# step.net
KiCad netlist of a schematic drawn in EAGLE
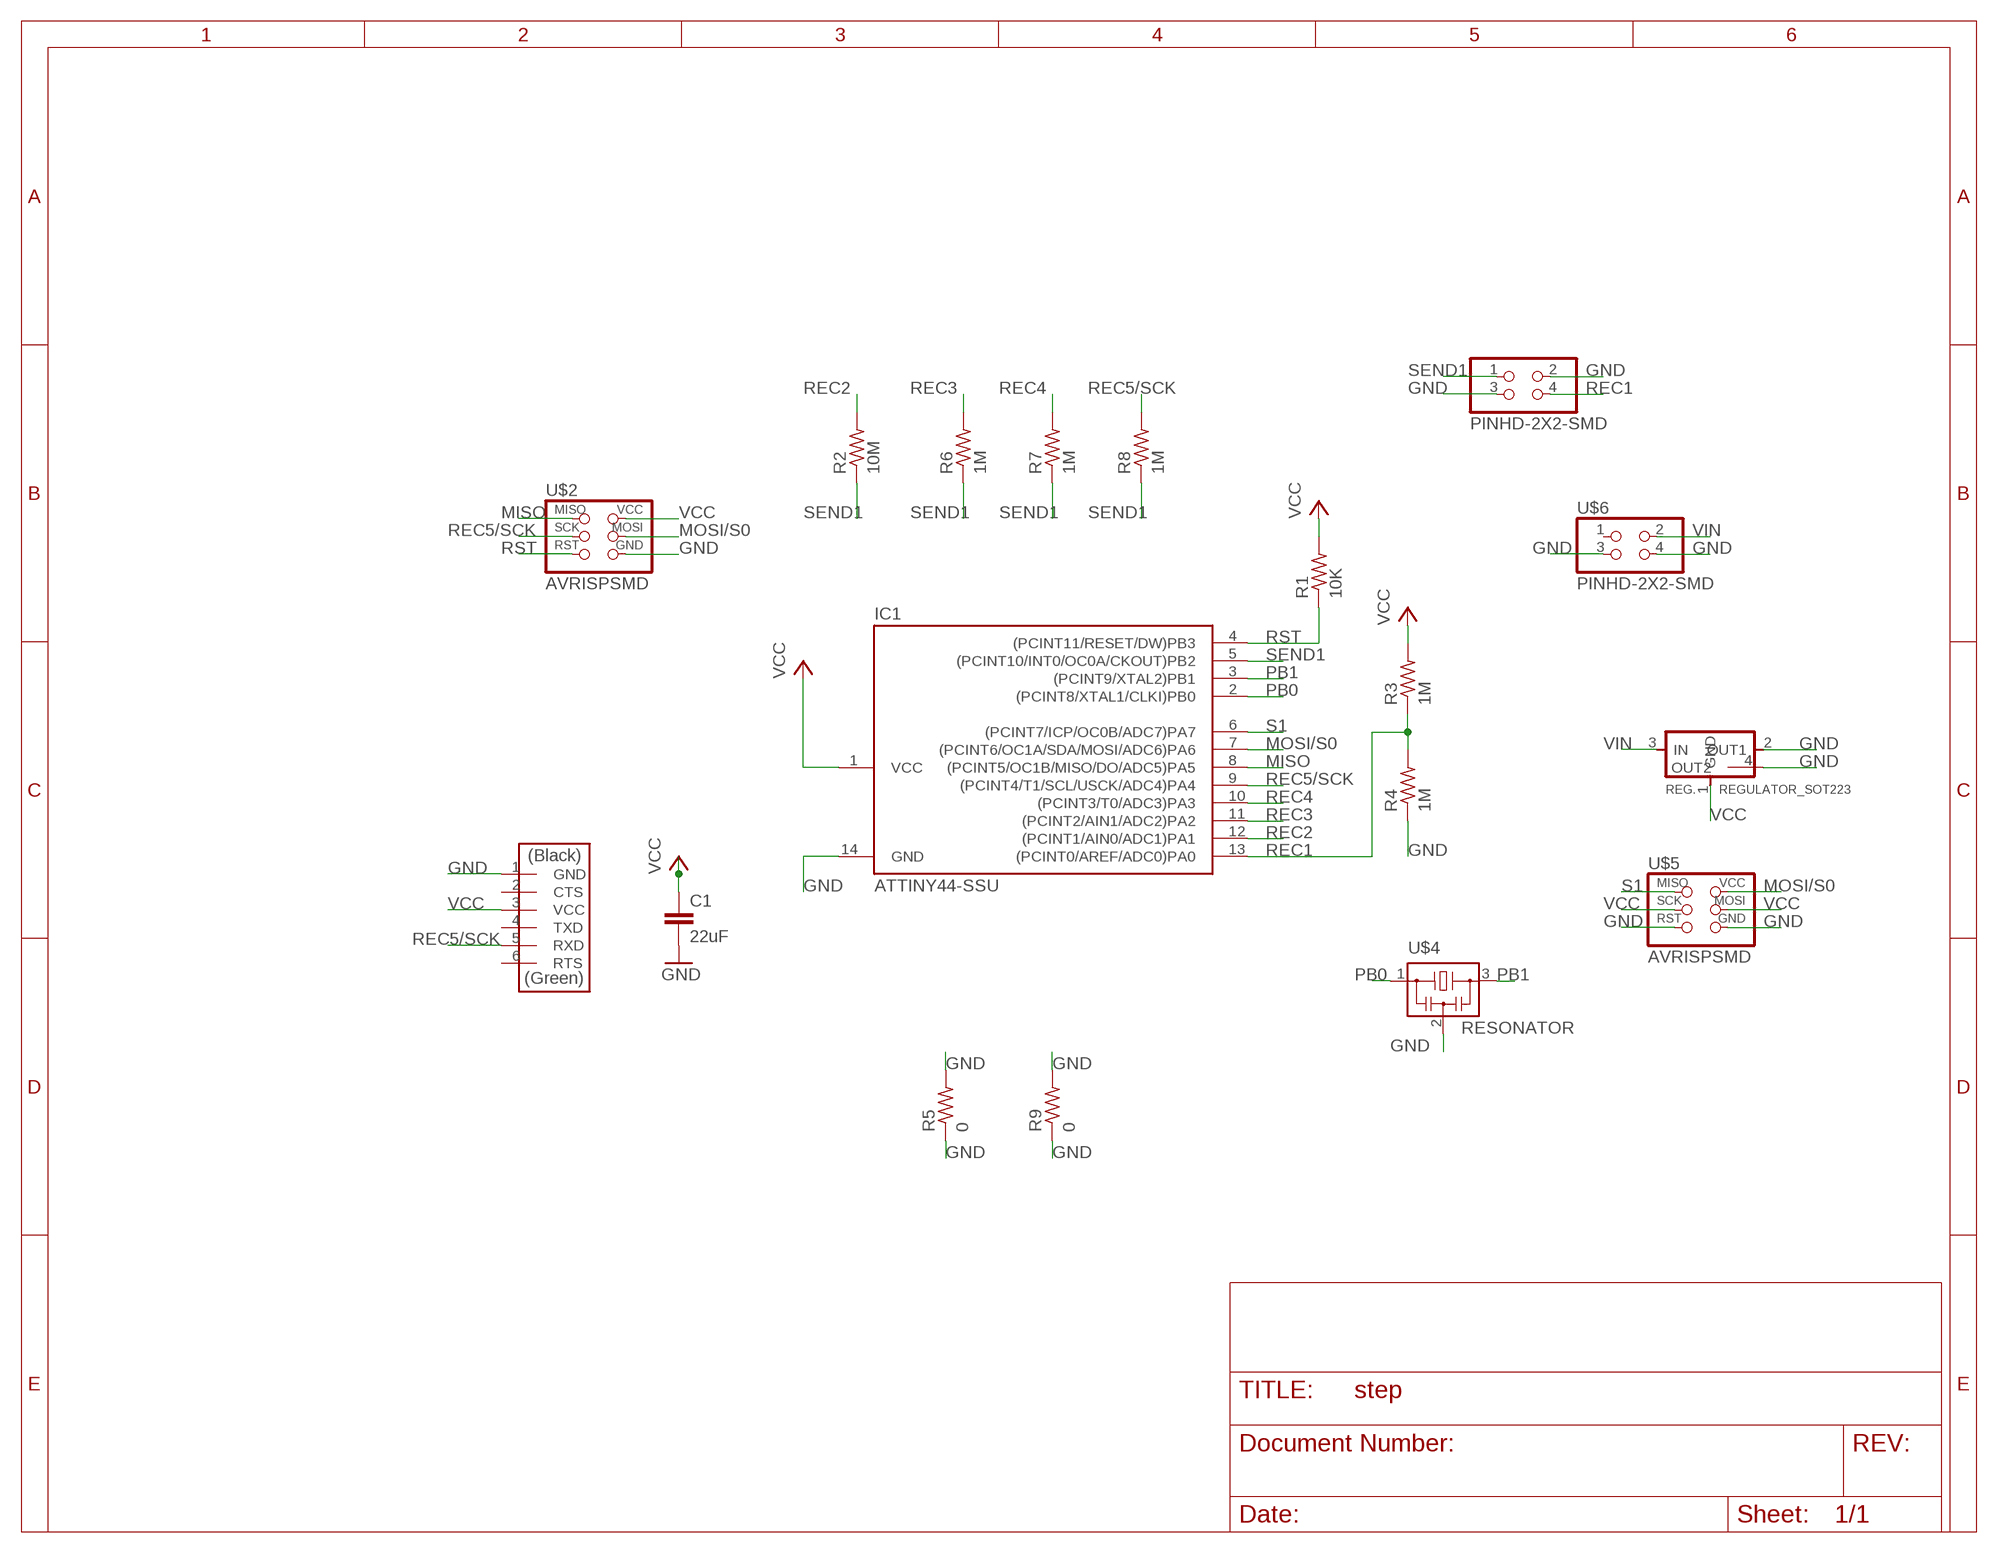
[diagram p0: schematic, sheet 1]

(export (version "E")
  (design (tool "Eeschema 10.0.6"))
  (components
    (comp (ref "C1")
      (value "22uF")
      (footprint "eagle-import:C1206")
      (libsource (lib "eagle-import") (part "C-EUC1206"))
    )
    (comp (ref "IC1")
      (value "ATTINY44-SSU")
      (footprint "eagle-import:SOIC14")
      (libsource (lib "eagle-import") (part "ATTINY44-SSU"))
    )
    (comp (ref "R1")
      (value "10K")
      (footprint "eagle-import:R1206FAB")
      (libsource (lib "eagle-import") (part "RES-US1206FAB"))
    )
    (comp (ref "R2")
      (value "10M")
      (footprint "eagle-import:R1206FAB")
      (libsource (lib "eagle-import") (part "RES-US1206FAB"))
    )
    (comp (ref "R3")
      (value "1M")
      (footprint "eagle-import:R1206FAB")
      (libsource (lib "eagle-import") (part "RES-US1206FAB"))
    )
    (comp (ref "R4")
      (value "1M")
      (footprint "eagle-import:R1206FAB")
      (libsource (lib "eagle-import") (part "RES-US1206FAB"))
    )
    (comp (ref "R5")
      (value "0")
      (footprint "eagle-import:R1206FAB")
      (libsource (lib "eagle-import") (part "RES-US1206FAB"))
    )
    (comp (ref "R6")
      (value "1M")
      (footprint "eagle-import:R1206FAB")
      (libsource (lib "eagle-import") (part "RES-US1206FAB"))
    )
    (comp (ref "R7")
      (value "1M")
      (footprint "eagle-import:R1206FAB")
      (libsource (lib "eagle-import") (part "RES-US1206FAB"))
    )
    (comp (ref "R8")
      (value "1M")
      (footprint "eagle-import:R1206FAB")
      (libsource (lib "eagle-import") (part "RES-US1206FAB"))
    )
    (comp (ref "R9")
      (value "0")
      (footprint "eagle-import:R1206FAB")
      (libsource (lib "eagle-import") (part "RES-US1206FAB"))
    )
    (comp (ref "REG.")
      (value "REGULATOR_SOT223")
      (footprint "eagle-import:SOT223")
      (libsource (lib "eagle-import") (part "REGULATOR_SOT223"))
    )
    (comp (ref "STEP/GND-SMD")
      (value "PINHD-2X2-SMD")
      (footprint "eagle-import:2X02SMD")
      (libsource (lib "eagle-import") (part "PINHD-2X2-SMD"))
    )
    (comp (ref "U$1")
      (value "FTDI-SMD-HEADER")
      (footprint "eagle-import:1X06SMD")
      (libsource (lib "eagle-import") (part "FTDI-SMD-HEADER"))
    )
    (comp (ref "U$2")
      (value "AVRISPSMD")
      (footprint "eagle-import:2X03SMD")
      (libsource (lib "eagle-import") (part "AVRISPSMD"))
    )
    (comp (ref "U$4")
      (value "RESONATOR")
      (footprint "eagle-import:EFOBM")
      (libsource (lib "eagle-import") (part "RESONATOR"))
    )
    (comp (ref "U$5")
      (value "AVRISPSMD")
      (footprint "eagle-import:2X03SMD")
      (libsource (lib "eagle-import") (part "AVRISPSMD"))
    )
    (comp (ref "U$6")
      (value "PINHD-2X2-SMD")
      (footprint "eagle-import:2X02SMD")
      (libsource (lib "eagle-import") (part "PINHD-2X2-SMD"))
    )
  )
  (nets
    (net (code "1") (name "/MISO") (class "Default")
      (node (ref "IC1") (pin "8") (pinfunction "(PCINT5/OC1B/MISO/DO/ADC5)PA5_8") (pintype "bidirectional"))
      (node (ref "U$2") (pin "1") (pinfunction "MISO_1") (pintype "passive"))
    )
    (net (code "2") (name "/MOSI{slash}S0") (class "Default")
      (node (ref "IC1") (pin "7") (pinfunction "(PCINT6/OC1A/SDA/MOSI/ADC6)PA6_7") (pintype "bidirectional"))
      (node (ref "U$2") (pin "4") (pinfunction "MOSI_4") (pintype "passive"))
      (node (ref "U$5") (pin "2") (pinfunction "VCC_2") (pintype "passive"))
    )
    (net (code "3") (name "/PB0") (class "Default")
      (node (ref "IC1") (pin "2") (pinfunction "(PCINT8/XTAL1/CLKI)PB0_2") (pintype "bidirectional"))
      (node (ref "U$4") (pin "1") (pinfunction "1_1") (pintype "passive"))
    )
    (net (code "4") (name "/PB1") (class "Default")
      (node (ref "IC1") (pin "3") (pinfunction "(PCINT9/XTAL2)PB1_3") (pintype "bidirectional"))
      (node (ref "U$4") (pin "3") (pinfunction "3_3") (pintype "passive"))
    )
    (net (code "5") (name "/REC1") (class "Default")
      (node (ref "IC1") (pin "13") (pinfunction "(PCINT0/AREF/ADC0)PA0_13") (pintype "bidirectional"))
      (node (ref "R3") (pin "1") (pinfunction "1_1") (pintype "passive"))
      (node (ref "R4") (pin "2") (pinfunction "2_2") (pintype "passive"))
      (node (ref "STEP/GND-SMD") (pin "4") (pinfunction "4_4") (pintype "passive"))
    )
    (net (code "6") (name "/REC2") (class "Default")
      (node (ref "IC1") (pin "12") (pinfunction "(PCINT1/AIN0/ADC1)PA1_12") (pintype "bidirectional"))
      (node (ref "R2") (pin "2") (pinfunction "2_2") (pintype "passive"))
    )
    (net (code "7") (name "/REC3") (class "Default")
      (node (ref "IC1") (pin "11") (pinfunction "(PCINT2/AIN1/ADC2)PA2_11") (pintype "bidirectional"))
      (node (ref "R6") (pin "2") (pinfunction "2_2") (pintype "passive"))
    )
    (net (code "8") (name "/REC4") (class "Default")
      (node (ref "IC1") (pin "10") (pinfunction "(PCINT3/T0/ADC3)PA3_10") (pintype "bidirectional"))
      (node (ref "R7") (pin "2") (pinfunction "2_2") (pintype "passive"))
    )
    (net (code "9") (name "/REC5{slash}SCK") (class "Default")
      (node (ref "IC1") (pin "9") (pinfunction "(PCINT4/T1/SCL/USCK/ADC4)PA4_9") (pintype "bidirectional"))
      (node (ref "R8") (pin "2") (pinfunction "2_2") (pintype "passive"))
      (node (ref "U$1") (pin "5") (pinfunction "RXD_5") (pintype "bidirectional"))
      (node (ref "U$2") (pin "3") (pinfunction "SCK_3") (pintype "passive"))
    )
    (net (code "10") (name "/RST") (class "Default")
      (node (ref "IC1") (pin "4") (pinfunction "(PCINT11/RESET/DW)PB3_4") (pintype "bidirectional"))
      (node (ref "R1") (pin "1") (pinfunction "1_1") (pintype "passive"))
      (node (ref "U$2") (pin "5") (pinfunction "RST_5") (pintype "passive"))
    )
    (net (code "11") (name "/S1") (class "Default")
      (node (ref "IC1") (pin "6") (pinfunction "(PCINT7/ICP/OC0B/ADC7)PA7_6") (pintype "bidirectional"))
      (node (ref "U$5") (pin "1") (pinfunction "MISO_1") (pintype "passive"))
    )
    (net (code "12") (name "/SEND1") (class "Default")
      (node (ref "IC1") (pin "5") (pinfunction "(PCINT10/INT0/OC0A/CKOUT)PB2_5") (pintype "bidirectional"))
      (node (ref "R2") (pin "1") (pinfunction "1_1") (pintype "passive"))
      (node (ref "R6") (pin "1") (pinfunction "1_1") (pintype "passive"))
      (node (ref "R7") (pin "1") (pinfunction "1_1") (pintype "passive"))
      (node (ref "R8") (pin "1") (pinfunction "1_1") (pintype "passive"))
      (node (ref "STEP/GND-SMD") (pin "1") (pinfunction "1_1") (pintype "passive"))
    )
    (net (code "13") (name "/VIN") (class "Default")
      (node (ref "REG.") (pin "3") (pinfunction "IN_3") (pintype "bidirectional"))
      (node (ref "U$6") (pin "2") (pinfunction "2_2") (pintype "passive"))
    )
    (net (code "14") (name "GND") (class "Default")
      (node (ref "C1") (pin "2") (pinfunction "2_2") (pintype "passive"))
      (node (ref "IC1") (pin "14") (pinfunction "GND_14") (pintype "power_in"))
      (node (ref "R4") (pin "1") (pinfunction "1_1") (pintype "passive"))
      (node (ref "R5") (pin "1") (pinfunction "1_1") (pintype "passive"))
      (node (ref "R5") (pin "2") (pinfunction "2_2") (pintype "passive"))
      (node (ref "R9") (pin "1") (pinfunction "1_1") (pintype "passive"))
      (node (ref "R9") (pin "2") (pinfunction "2_2") (pintype "passive"))
      (node (ref "REG.") (pin "2") (pinfunction "OUT1_2") (pintype "bidirectional"))
      (node (ref "REG.") (pin "4") (pinfunction "OUT2_4") (pintype "bidirectional"))
      (node (ref "STEP/GND-SMD") (pin "2") (pinfunction "2_2") (pintype "passive"))
      (node (ref "STEP/GND-SMD") (pin "3") (pinfunction "3_3") (pintype "passive"))
      (node (ref "U$1") (pin "1") (pinfunction "GND_1") (pintype "bidirectional"))
      (node (ref "U$2") (pin "6") (pinfunction "GND_6") (pintype "passive"))
      (node (ref "U$4") (pin "2") (pinfunction "2_2") (pintype "passive"))
      (node (ref "U$5") (pin "5") (pinfunction "RST_5") (pintype "passive"))
      (node (ref "U$5") (pin "6") (pinfunction "GND_6") (pintype "passive"))
      (node (ref "U$6") (pin "3") (pinfunction "3_3") (pintype "passive"))
      (node (ref "U$6") (pin "4") (pinfunction "4_4") (pintype "passive"))
    )
    (net (code "15") (name "VCC") (class "Default")
      (node (ref "C1") (pin "1") (pinfunction "1_1") (pintype "passive"))
      (node (ref "IC1") (pin "1") (pinfunction "VCC_1") (pintype "power_in"))
      (node (ref "R1") (pin "2") (pinfunction "2_2") (pintype "passive"))
      (node (ref "R3") (pin "2") (pinfunction "2_2") (pintype "passive"))
      (node (ref "REG.") (pin "1") (pinfunction "GND_1") (pintype "bidirectional"))
      (node (ref "U$1") (pin "3") (pinfunction "VCC_3") (pintype "bidirectional"))
      (node (ref "U$2") (pin "2") (pinfunction "VCC_2") (pintype "passive"))
      (node (ref "U$5") (pin "3") (pinfunction "SCK_3") (pintype "passive"))
      (node (ref "U$5") (pin "4") (pinfunction "MOSI_4") (pintype "passive"))
    )
    (net (code "16") (name "unconnected-(U$1-CTS-Pad2)") (class "Default")
      (node (ref "U$1") (pin "2") (pinfunction "CTS_2") (pintype "bidirectional"))
    )
    (net (code "17") (name "unconnected-(U$1-RTS-Pad6)") (class "Default")
      (node (ref "U$1") (pin "6") (pinfunction "RTS_6") (pintype "bidirectional"))
    )
    (net (code "18") (name "unconnected-(U$1-TXD-Pad4)") (class "Default")
      (node (ref "U$1") (pin "4") (pinfunction "TXD_4") (pintype "bidirectional"))
    )
    (net (code "19") (name "unconnected-(U$6-Pad1)") (class "Default")
      (node (ref "U$6") (pin "1") (pinfunction "1_1") (pintype "passive"))
    )
  )
)
